# 03_ADV7511_HDMI_OUT.net
KiCad netlist of a schematic drawn in Altium Designer
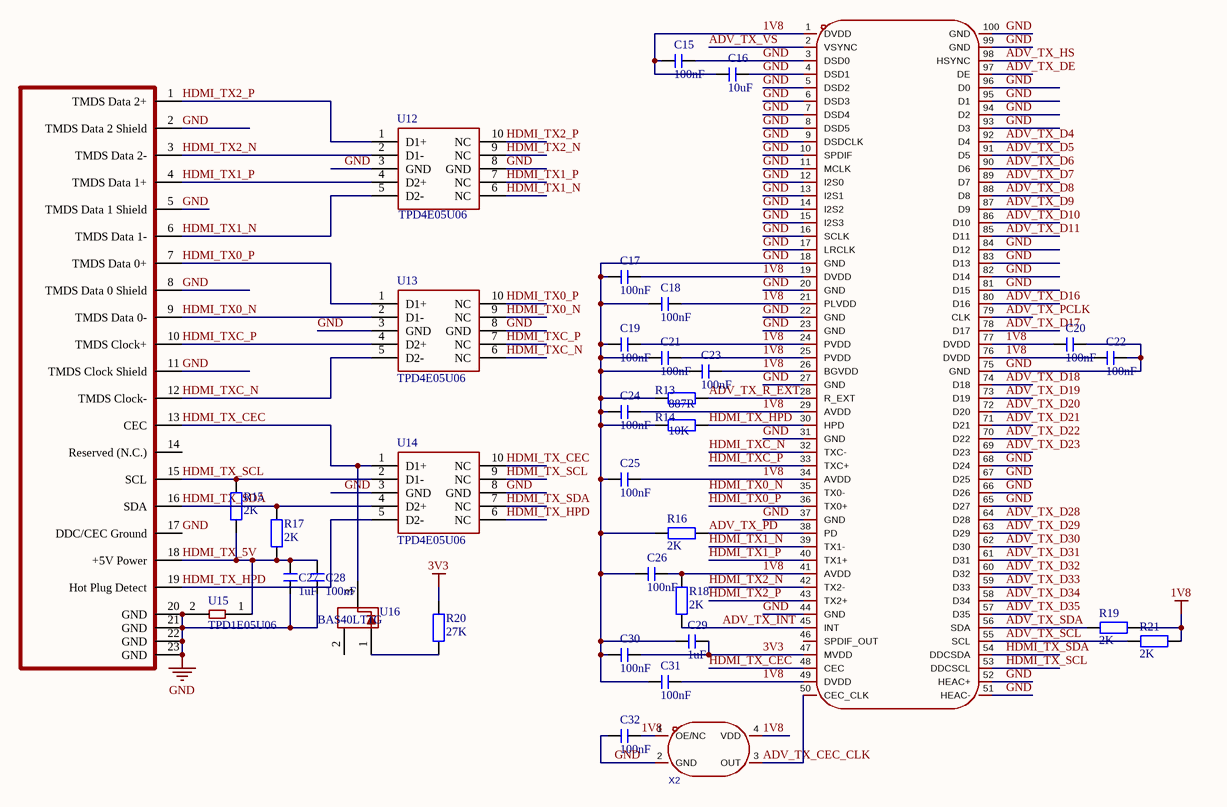
[diagram p0: 03_ADV7511_HDMI_OUT.SchDoc]

(export (version "E")
  (design (tool "Eeschema 10.0.6"))
  (components
    (comp (ref "C15")
      (value "100nF")
      (footprint "C 0603_L")
      (description "贴片电容")
      (libsource (lib "Xilinx_XCKU040_Ext_Board") (part "C"))
    )
    (comp (ref "C16")
      (value "10uF")
      (footprint "C 0603_L")
      (description "贴片电容")
      (libsource (lib "Xilinx_XCKU040_Ext_Board") (part "C"))
    )
    (comp (ref "C17")
      (value "100nF")
      (footprint "C 0603_L")
      (description "贴片电容")
      (libsource (lib "Xilinx_XCKU040_Ext_Board") (part "C"))
    )
    (comp (ref "C18")
      (value "100nF")
      (footprint "C 0603_L")
      (description "贴片电容")
      (libsource (lib "Xilinx_XCKU040_Ext_Board") (part "C"))
    )
    (comp (ref "C19")
      (value "100nF")
      (footprint "C 0603_L")
      (description "贴片电容")
      (libsource (lib "Xilinx_XCKU040_Ext_Board") (part "C"))
    )
    (comp (ref "C20")
      (value "100nF")
      (footprint "C 0603_L")
      (description "贴片电容")
      (libsource (lib "Xilinx_XCKU040_Ext_Board") (part "C"))
    )
    (comp (ref "C21")
      (value "100nF")
      (footprint "C 0603_L")
      (description "贴片电容")
      (libsource (lib "Xilinx_XCKU040_Ext_Board") (part "C"))
    )
    (comp (ref "C22")
      (value "100nF")
      (footprint "C 0603_L")
      (description "贴片电容")
      (libsource (lib "Xilinx_XCKU040_Ext_Board") (part "C"))
    )
    (comp (ref "C23")
      (value "100nF")
      (footprint "C 0603_L")
      (description "贴片电容")
      (libsource (lib "Xilinx_XCKU040_Ext_Board") (part "C"))
    )
    (comp (ref "C24")
      (value "100nF")
      (footprint "C 0603_L")
      (description "贴片电容")
      (libsource (lib "Xilinx_XCKU040_Ext_Board") (part "C"))
    )
    (comp (ref "C25")
      (value "100nF")
      (footprint "C 0603_L")
      (description "贴片电容")
      (libsource (lib "Xilinx_XCKU040_Ext_Board") (part "C"))
    )
    (comp (ref "C26")
      (value "100nF")
      (footprint "C 0603_L")
      (description "贴片电容")
      (libsource (lib "Xilinx_XCKU040_Ext_Board") (part "C"))
    )
    (comp (ref "C27")
      (value "1uF")
      (footprint "C 0603_L")
      (description "贴片电容")
      (libsource (lib "Xilinx_XCKU040_Ext_Board") (part "C"))
    )
    (comp (ref "C28")
      (value "100nF")
      (footprint "C 0603_L")
      (description "贴片电容")
      (libsource (lib "Xilinx_XCKU040_Ext_Board") (part "C"))
    )
    (comp (ref "C29")
      (value "1uF")
      (footprint "C 0603_L")
      (description "贴片电容")
      (libsource (lib "Xilinx_XCKU040_Ext_Board") (part "C"))
    )
    (comp (ref "C30")
      (value "100nF")
      (footprint "C 0603_L")
      (description "贴片电容")
      (libsource (lib "Xilinx_XCKU040_Ext_Board") (part "C"))
    )
    (comp (ref "C31")
      (value "100nF")
      (footprint "C 0603_L")
      (description "贴片电容")
      (libsource (lib "Xilinx_XCKU040_Ext_Board") (part "C"))
    )
    (comp (ref "C32")
      (value "100nF")
      (footprint "C 0603_L")
      (description "贴片电容")
      (libsource (lib "Xilinx_XCKU040_Ext_Board") (part "C"))
    )
    (comp (ref "R13")
      (value "887R")
      (footprint "R 0603_L")
      (description "贴片电阻1%")
      (fields (field (name "版权归属") "来自淘宝 ID：黄晶宝石"))
      (libsource (lib "Xilinx_XCKU040_Ext_Board") (part "R"))
    )
    (comp (ref "R14")
      (value "10K")
      (footprint "R 0603_L")
      (description "贴片电阻")
      (fields (field (name "版权归属") "来自淘宝 ID：黄晶宝石"))
      (libsource (lib "Xilinx_XCKU040_Ext_Board") (part "R"))
    )
    (comp (ref "R15")
      (value "2K")
      (footprint "R 0603_L")
      (description "贴片电阻")
      (fields (field (name "版权归属") "来自淘宝 ID：黄晶宝石"))
      (libsource (lib "Xilinx_XCKU040_Ext_Board") (part "R"))
    )
    (comp (ref "R16")
      (value "2K")
      (footprint "R 0603_L")
      (description "贴片电阻")
      (fields (field (name "版权归属") "来自淘宝 ID：黄晶宝石"))
      (libsource (lib "Xilinx_XCKU040_Ext_Board") (part "R"))
    )
    (comp (ref "R17")
      (value "2K")
      (footprint "R 0603_L")
      (description "贴片电阻")
      (fields (field (name "版权归属") "来自淘宝 ID：黄晶宝石"))
      (libsource (lib "Xilinx_XCKU040_Ext_Board") (part "R"))
    )
    (comp (ref "R18")
      (value "2K")
      (footprint "R 0603_L")
      (description "贴片电阻")
      (fields (field (name "版权归属") "来自淘宝 ID：黄晶宝石"))
      (libsource (lib "Xilinx_XCKU040_Ext_Board") (part "R"))
    )
    (comp (ref "R19")
      (value "2K")
      (footprint "R 0603_L")
      (description "贴片电阻")
      (fields (field (name "版权归属") "来自淘宝 ID：黄晶宝石"))
      (libsource (lib "Xilinx_XCKU040_Ext_Board") (part "R"))
    )
    (comp (ref "R20")
      (value "27K")
      (footprint "R 0603_L")
      (description "贴片电阻")
      (fields (field (name "版权归属") "来自淘宝 ID：黄晶宝石"))
      (libsource (lib "Xilinx_XCKU040_Ext_Board") (part "R"))
    )
    (comp (ref "R21")
      (value "2K")
      (footprint "R 0603_L")
      (description "贴片电阻")
      (fields (field (name "版权归属") "来自淘宝 ID：黄晶宝石"))
      (libsource (lib "Xilinx_XCKU040_Ext_Board") (part "R"))
    )
    (comp (ref "U5")
      (value "adv7511kstz")
      (footprint "LQFP-100_L14.0-W14.0-P0.50-LS16.0-BL")
      (description "接口类型:I2S；I2C;数据速率:-;")
      (fields (field (name "MANUFACTURER") "ADI(亚德诺)") (field (name "MANUFACTURERPART") "ADV7511KSTZ"))
      (libsource (lib "0.0self_build") (part "adv7511kstz"))
    )
    (comp (ref "U12")
      (value "TPD4E05U06")
      (footprint "TPD4E05U06DQAR")
      (description "TVS 5V ESD")
      (libsource (lib "Xilinx_XCKU040_Ext_Board") (part "TPD4E05U06"))
    )
    (comp (ref "U13")
      (value "TPD4E05U06")
      (footprint "TPD4E05U06DQAR")
      (description "TVS 5V ESD")
      (libsource (lib "Xilinx_XCKU040_Ext_Board") (part "TPD4E05U06"))
    )
    (comp (ref "U14")
      (value "TPD4E05U06")
      (footprint "TPD4E05U06DQAR")
      (description "TVS 5V ESD")
      (libsource (lib "Xilinx_XCKU040_Ext_Board") (part "TPD4E05U06"))
    )
    (comp (ref "U15")
      (value "TPD1E05U06")
      (footprint "TPD1E05U06")
      (description "单通道ESD")
      (libsource (lib "Xilinx_XCKU040_Ext_Board") (part "TPD1E05U06"))
    )
    (comp (ref "U16")
      (value "BAS40LT1G")
      (footprint "BAS40LT1G")
      (description "肖特基二极管")
      (libsource (lib "Xilinx_XCKU040_Ext_Board") (part "BAS40LT1G"))
    )
    (comp (ref "USB3")
      (value "hdmi-001s")
      (footprint "HDMI-SMD_HDMI-001S")
      (description "19PIN A型前插后贴HDMI插座 铜壳")
      (fields (field (name "MANUFACTURER") "XUNPU(讯普)") (field (name "MANUFACTURERPART") "HDMI-001S"))
      (libsource (lib "Xilinx_XCKU040_Ext_Board") (part "hdmi-001s"))
    )
    (comp (ref "X2")
      (value "ot322512mjba4sl")
      (footprint "OSC-SMD_4P-L3.2-W2.5-BL")
      (description "频率:12MHz;常温频差:±10ppm;输出模式:CMOS;工作电压:1.8V~3.3V;频率稳定度:±20ppm;")
      (fields (field (name "MANUFACTURER") "YXC(扬兴晶振)") (field (name "MANUFACTURERPART") "OT322512MJBA4SL"))
      (libsource (lib "Xilinx_XCKU040_Ext_Board") (part "ot322512mjba4sl"))
    )
  )
  (nets
    (net (code "1") (name "/ADV_TX_CEC_CLK") (class "Default")
      (node (ref "U5") (pin "50") (pinfunction "CEC_CLK_50") (pintype "passive"))
      (node (ref "X2") (pin "3") (pinfunction "OUT_3") (pintype "passive"))
    )
    (net (code "2") (name "/ADV_TX_D4") (class "Default")
      (node (ref "U5") (pin "92") (pinfunction "D4_92") (pintype "passive"))
    )
    (net (code "3") (name "/ADV_TX_D5") (class "Default")
      (node (ref "U5") (pin "91") (pinfunction "D5_91") (pintype "passive"))
    )
    (net (code "4") (name "/ADV_TX_D6") (class "Default")
      (node (ref "U5") (pin "90") (pinfunction "D6_90") (pintype "passive"))
    )
    (net (code "5") (name "/ADV_TX_D7") (class "Default")
      (node (ref "U5") (pin "89") (pinfunction "D7_89") (pintype "passive"))
    )
    (net (code "6") (name "/ADV_TX_D8") (class "Default")
      (node (ref "U5") (pin "88") (pinfunction "D8_88") (pintype "passive"))
    )
    (net (code "7") (name "/ADV_TX_D9") (class "Default")
      (node (ref "U5") (pin "87") (pinfunction "D9_87") (pintype "passive"))
    )
    (net (code "8") (name "/ADV_TX_D10") (class "Default")
      (node (ref "U5") (pin "86") (pinfunction "D10_86") (pintype "passive"))
    )
    (net (code "9") (name "/ADV_TX_D11") (class "Default")
      (node (ref "U5") (pin "85") (pinfunction "D11_85") (pintype "passive"))
    )
    (net (code "10") (name "/ADV_TX_D16") (class "Default")
      (node (ref "U5") (pin "80") (pinfunction "D16_80") (pintype "passive"))
    )
    (net (code "11") (name "/ADV_TX_D17") (class "Default")
      (node (ref "U5") (pin "78") (pinfunction "D17_78") (pintype "passive"))
    )
    (net (code "12") (name "/ADV_TX_D18") (class "Default")
      (node (ref "U5") (pin "74") (pinfunction "D18_74") (pintype "passive"))
    )
    (net (code "13") (name "/ADV_TX_D19") (class "Default")
      (node (ref "U5") (pin "73") (pinfunction "D19_73") (pintype "passive"))
    )
    (net (code "14") (name "/ADV_TX_D20") (class "Default")
      (node (ref "U5") (pin "72") (pinfunction "D20_72") (pintype "passive"))
    )
    (net (code "15") (name "/ADV_TX_D21") (class "Default")
      (node (ref "U5") (pin "71") (pinfunction "D21_71") (pintype "passive"))
    )
    (net (code "16") (name "/ADV_TX_D22") (class "Default")
      (node (ref "U5") (pin "70") (pinfunction "D22_70") (pintype "passive"))
    )
    (net (code "17") (name "/ADV_TX_D23") (class "Default")
      (node (ref "U5") (pin "69") (pinfunction "D23_69") (pintype "passive"))
    )
    (net (code "18") (name "/ADV_TX_D28") (class "Default")
      (node (ref "U5") (pin "64") (pinfunction "D28_64") (pintype "passive"))
    )
    (net (code "19") (name "/ADV_TX_D29") (class "Default")
      (node (ref "U5") (pin "63") (pinfunction "D29_63") (pintype "passive"))
    )
    (net (code "20") (name "/ADV_TX_D30") (class "Default")
      (node (ref "U5") (pin "62") (pinfunction "D30_62") (pintype "passive"))
    )
    (net (code "21") (name "/ADV_TX_D31") (class "Default")
      (node (ref "U5") (pin "61") (pinfunction "D31_61") (pintype "passive"))
    )
    (net (code "22") (name "/ADV_TX_D32") (class "Default")
      (node (ref "U5") (pin "60") (pinfunction "D32_60") (pintype "passive"))
    )
    (net (code "23") (name "/ADV_TX_D33") (class "Default")
      (node (ref "U5") (pin "59") (pinfunction "D33_59") (pintype "passive"))
    )
    (net (code "24") (name "/ADV_TX_D34") (class "Default")
      (node (ref "U5") (pin "58") (pinfunction "D34_58") (pintype "passive"))
    )
    (net (code "25") (name "/ADV_TX_D35") (class "Default")
      (node (ref "U5") (pin "57") (pinfunction "D35_57") (pintype "passive"))
    )
    (net (code "26") (name "/ADV_TX_DE") (class "Default")
      (node (ref "U5") (pin "97") (pinfunction "DE_97") (pintype "passive"))
    )
    (net (code "27") (name "/ADV_TX_HS") (class "Default")
      (node (ref "U5") (pin "98") (pinfunction "HSYNC_98") (pintype "passive"))
    )
    (net (code "28") (name "/ADV_TX_INT") (class "Default")
      (node (ref "R18") (pin "2") (pinfunction "2_2") (pintype "passive"))
      (node (ref "U5") (pin "45") (pinfunction "INT_45") (pintype "passive"))
    )
    (net (code "29") (name "/ADV_TX_PCLK") (class "Default")
      (node (ref "U5") (pin "79") (pinfunction "CLK_79") (pintype "passive"))
    )
    (net (code "30") (name "/ADV_TX_PD") (class "Default")
      (node (ref "R16") (pin "2") (pinfunction "2_2") (pintype "passive"))
      (node (ref "U5") (pin "38") (pinfunction "PD_38") (pintype "passive"))
    )
    (net (code "31") (name "/ADV_TX_R_EXT") (class "Default")
      (node (ref "R13") (pin "2") (pinfunction "2_2") (pintype "passive"))
      (node (ref "U5") (pin "28") (pinfunction "R_EXT_28") (pintype "passive"))
    )
    (net (code "32") (name "/ADV_TX_SCL") (class "Default")
      (node (ref "R21") (pin "1") (pinfunction "1_1") (pintype "passive"))
      (node (ref "U5") (pin "55") (pinfunction "SCL_55") (pintype "passive"))
    )
    (net (code "33") (name "/ADV_TX_SDA") (class "Default")
      (node (ref "R19") (pin "1") (pinfunction "1_1") (pintype "passive"))
      (node (ref "U5") (pin "56") (pinfunction "SDA_56") (pintype "passive"))
    )
    (net (code "34") (name "/ADV_TX_VS") (class "Default")
      (node (ref "U5") (pin "2") (pinfunction "VSYNC_2") (pintype "passive"))
    )
    (net (code "35") (name "/HDMI_TX0_N") (class "Default")
      (node (ref "U13") (pin "2") (pinfunction "D1-_2") (pintype "passive"))
      (node (ref "U13") (pin "9") (pinfunction "NC_9") (pintype "passive"))
      (node (ref "U5") (pin "35") (pinfunction "TX0-_35") (pintype "passive"))
      (node (ref "USB3") (pin "9") (pinfunction "TMDS_Data_0-_9") (pintype "passive"))
    )
    (net (code "36") (name "/HDMI_TX0_P") (class "Default")
      (node (ref "U13") (pin "1") (pinfunction "D1+_1") (pintype "passive"))
      (node (ref "U13") (pin "10") (pinfunction "NC_10") (pintype "passive"))
      (node (ref "U5") (pin "36") (pinfunction "TX0+_36") (pintype "passive"))
      (node (ref "USB3") (pin "7") (pinfunction "TMDS_Data_0+_7") (pintype "passive"))
    )
    (net (code "37") (name "/HDMI_TX1_N") (class "Default")
      (node (ref "U12") (pin "5") (pinfunction "D2-_5") (pintype "passive"))
      (node (ref "U12") (pin "6") (pinfunction "NC_6") (pintype "passive"))
      (node (ref "U5") (pin "39") (pinfunction "TX1-_39") (pintype "passive"))
      (node (ref "USB3") (pin "6") (pinfunction "TMDS_Data_1-_6") (pintype "passive"))
    )
    (net (code "38") (name "/HDMI_TX1_P") (class "Default")
      (node (ref "U12") (pin "4") (pinfunction "D2+_4") (pintype "passive"))
      (node (ref "U12") (pin "7") (pinfunction "NC_7") (pintype "passive"))
      (node (ref "U5") (pin "40") (pinfunction "TX1+_40") (pintype "passive"))
      (node (ref "USB3") (pin "4") (pinfunction "TMDS_Data_1+_4") (pintype "passive"))
    )
    (net (code "39") (name "/HDMI_TX2_N") (class "Default")
      (node (ref "U12") (pin "2") (pinfunction "D1-_2") (pintype "passive"))
      (node (ref "U12") (pin "9") (pinfunction "NC_9") (pintype "passive"))
      (node (ref "U5") (pin "42") (pinfunction "TX2-_42") (pintype "passive"))
      (node (ref "USB3") (pin "3") (pinfunction "TMDS_Data_2-_3") (pintype "passive"))
    )
    (net (code "40") (name "/HDMI_TX2_P") (class "Default")
      (node (ref "U12") (pin "1") (pinfunction "D1+_1") (pintype "passive"))
      (node (ref "U12") (pin "10") (pinfunction "NC_10") (pintype "passive"))
      (node (ref "U5") (pin "43") (pinfunction "TX2+_43") (pintype "passive"))
      (node (ref "USB3") (pin "1") (pinfunction "TMDS_Data_2+_1") (pintype "passive"))
    )
    (net (code "41") (name "/HDMI_TXC_N") (class "Default")
      (node (ref "U13") (pin "5") (pinfunction "D2-_5") (pintype "passive"))
      (node (ref "U13") (pin "6") (pinfunction "NC_6") (pintype "passive"))
      (node (ref "U5") (pin "32") (pinfunction "TXC-_32") (pintype "passive"))
      (node (ref "USB3") (pin "12") (pinfunction "TMDS_Clock-_12") (pintype "passive"))
    )
    (net (code "42") (name "/HDMI_TXC_P") (class "Default")
      (node (ref "U13") (pin "4") (pinfunction "D2+_4") (pintype "passive"))
      (node (ref "U13") (pin "7") (pinfunction "NC_7") (pintype "passive"))
      (node (ref "U5") (pin "33") (pinfunction "TXC+_33") (pintype "passive"))
      (node (ref "USB3") (pin "10") (pinfunction "TMDS_Clock+_10") (pintype "passive"))
    )
    (net (code "43") (name "/HDMI_TX_5V") (class "Default")
      (node (ref "C27") (pin "1") (pinfunction "1_1") (pintype "passive"))
      (node (ref "C28") (pin "1") (pinfunction "1_1") (pintype "passive"))
      (node (ref "R15") (pin "1") (pinfunction "1_1") (pintype "passive"))
      (node (ref "R17") (pin "1") (pinfunction "1_1") (pintype "passive"))
      (node (ref "U15") (pin "1") (pinfunction "IO_1") (pintype "passive"))
      (node (ref "USB3") (pin "18") (pinfunction "+5V_Power_18") (pintype "passive"))
    )
    (net (code "44") (name "/HDMI_TX_CEC") (class "Default")
      (node (ref "U14") (pin "1") (pinfunction "D1+_1") (pintype "passive"))
      (node (ref "U14") (pin "10") (pinfunction "NC_10") (pintype "passive"))
      (node (ref "U16") (pin "3") (pinfunction "3_3") (pintype "passive"))
      (node (ref "U5") (pin "48") (pinfunction "CEC_48") (pintype "passive"))
      (node (ref "USB3") (pin "13") (pinfunction "CEC_13") (pintype "passive"))
    )
    (net (code "45") (name "/HDMI_TX_HPD") (class "Default")
      (node (ref "R14") (pin "2") (pinfunction "2_2") (pintype "passive"))
      (node (ref "U14") (pin "5") (pinfunction "D2-_5") (pintype "passive"))
      (node (ref "U14") (pin "6") (pinfunction "NC_6") (pintype "passive"))
      (node (ref "U5") (pin "30") (pinfunction "HPD_30") (pintype "passive"))
      (node (ref "USB3") (pin "19") (pinfunction "Hot_Plug_Detect_19") (pintype "passive"))
    )
    (net (code "46") (name "/HDMI_TX_SCL") (class "Default")
      (node (ref "R15") (pin "2") (pinfunction "2_2") (pintype "passive"))
      (node (ref "U14") (pin "2") (pinfunction "D1-_2") (pintype "passive"))
      (node (ref "U14") (pin "9") (pinfunction "NC_9") (pintype "passive"))
      (node (ref "U5") (pin "53") (pinfunction "DDCSCL_53") (pintype "passive"))
      (node (ref "USB3") (pin "15") (pinfunction "SCL_15") (pintype "passive"))
    )
    (net (code "47") (name "/HDMI_TX_SDA") (class "Default")
      (node (ref "R17") (pin "2") (pinfunction "2_2") (pintype "passive"))
      (node (ref "U14") (pin "4") (pinfunction "D2+_4") (pintype "passive"))
      (node (ref "U14") (pin "7") (pinfunction "NC_7") (pintype "passive"))
      (node (ref "U5") (pin "54") (pinfunction "DDCSDA_54") (pintype "passive"))
      (node (ref "USB3") (pin "16") (pinfunction "SDA_16") (pintype "passive"))
    )
    (net (code "48") (name "1V8") (class "Default")
      (node (ref "C15") (pin "2") (pinfunction "2_2") (pintype "passive"))
      (node (ref "C16") (pin "2") (pinfunction "2_2") (pintype "passive"))
      (node (ref "C17") (pin "1") (pinfunction "1_1") (pintype "passive"))
      (node (ref "C18") (pin "1") (pinfunction "1_1") (pintype "passive"))
      (node (ref "C19") (pin "1") (pinfunction "1_1") (pintype "passive"))
      (node (ref "C20") (pin "2") (pinfunction "2_2") (pintype "passive"))
      (node (ref "C21") (pin "1") (pinfunction "1_1") (pintype "passive"))
      (node (ref "C22") (pin "2") (pinfunction "2_2") (pintype "passive"))
      (node (ref "C23") (pin "1") (pinfunction "1_1") (pintype "passive"))
      (node (ref "C24") (pin "1") (pinfunction "1_1") (pintype "passive"))
      (node (ref "C25") (pin "1") (pinfunction "1_1") (pintype "passive"))
      (node (ref "C26") (pin "1") (pinfunction "1_1") (pintype "passive"))
      (node (ref "C31") (pin "1") (pinfunction "1_1") (pintype "passive"))
      (node (ref "C32") (pin "1") (pinfunction "1_1") (pintype "passive"))
      (node (ref "R18") (pin "1") (pinfunction "1_1") (pintype "passive"))
      (node (ref "R19") (pin "2") (pinfunction "2_2") (pintype "passive"))
      (node (ref "R21") (pin "2") (pinfunction "2_2") (pintype "passive"))
      (node (ref "U5") (pin "1") (pinfunction "DVDD_1") (pintype "passive"))
      (node (ref "U5") (pin "19") (pinfunction "DVDD_19") (pintype "passive"))
      (node (ref "U5") (pin "21") (pinfunction "PLVDD_21") (pintype "passive"))
      (node (ref "U5") (pin "24") (pinfunction "PVDD_24") (pintype "passive"))
      (node (ref "U5") (pin "25") (pinfunction "PVDD_25") (pintype "passive"))
      (node (ref "U5") (pin "26") (pinfunction "BGVDD_26") (pintype "passive"))
      (node (ref "U5") (pin "29") (pinfunction "AVDD_29") (pintype "passive"))
      (node (ref "U5") (pin "34") (pinfunction "AVDD_34") (pintype "passive"))
      (node (ref "U5") (pin "41") (pinfunction "AVDD_41") (pintype "passive"))
      (node (ref "U5") (pin "49") (pinfunction "DVDD_49") (pintype "passive"))
      (node (ref "U5") (pin "76") (pinfunction "DVDD_76") (pintype "passive"))
      (node (ref "U5") (pin "77") (pinfunction "DVDD_77") (pintype "passive"))
      (node (ref "X2") (pin "1") (pinfunction "OE/NC_1") (pintype "passive"))
      (node (ref "X2") (pin "4") (pinfunction "VDD_4") (pintype "passive"))
    )
    (net (code "49") (name "3V3") (class "Default")
      (node (ref "C29") (pin "1") (pinfunction "1_1") (pintype "passive"))
      (node (ref "C30") (pin "1") (pinfunction "1_1") (pintype "passive"))
      (node (ref "R20") (pin "2") (pinfunction "2_2") (pintype "passive"))
      (node (ref "U5") (pin "47") (pinfunction "MVDD_47") (pintype "passive"))
    )
    (net (code "50") (name "GND") (class "Default")
      (node (ref "C15") (pin "1") (pinfunction "1_1") (pintype "passive"))
      (node (ref "C16") (pin "1") (pinfunction "1_1") (pintype "passive"))
      (node (ref "C17") (pin "2") (pinfunction "2_2") (pintype "passive"))
      (node (ref "C18") (pin "2") (pinfunction "2_2") (pintype "passive"))
      (node (ref "C19") (pin "2") (pinfunction "2_2") (pintype "passive"))
      (node (ref "C20") (pin "1") (pinfunction "1_1") (pintype "passive"))
      (node (ref "C21") (pin "2") (pinfunction "2_2") (pintype "passive"))
      (node (ref "C22") (pin "1") (pinfunction "1_1") (pintype "passive"))
      (node (ref "C23") (pin "2") (pinfunction "2_2") (pintype "passive"))
      (node (ref "C24") (pin "2") (pinfunction "2_2") (pintype "passive"))
      (node (ref "C25") (pin "2") (pinfunction "2_2") (pintype "passive"))
      (node (ref "C26") (pin "2") (pinfunction "2_2") (pintype "passive"))
      (node (ref "C27") (pin "2") (pinfunction "2_2") (pintype "passive"))
      (node (ref "C28") (pin "2") (pinfunction "2_2") (pintype "passive"))
      (node (ref "C29") (pin "2") (pinfunction "2_2") (pintype "passive"))
      (node (ref "C30") (pin "2") (pinfunction "2_2") (pintype "passive"))
      (node (ref "C31") (pin "2") (pinfunction "2_2") (pintype "passive"))
      (node (ref "C32") (pin "2") (pinfunction "2_2") (pintype "passive"))
      (node (ref "R13") (pin "1") (pinfunction "1_1") (pintype "passive"))
      (node (ref "R14") (pin "1") (pinfunction "1_1") (pintype "passive"))
      (node (ref "R16") (pin "1") (pinfunction "1_1") (pintype "passive"))
      (node (ref "U12") (pin "3") (pinfunction "GND_3") (pintype "passive"))
      (node (ref "U12") (pin "8") (pinfunction "GND_8") (pintype "passive"))
      (node (ref "U13") (pin "3") (pinfunction "GND_3") (pintype "passive"))
      (node (ref "U13") (pin "8") (pinfunction "GND_8") (pintype "passive"))
      (node (ref "U14") (pin "3") (pinfunction "GND_3") (pintype "passive"))
      (node (ref "U14") (pin "8") (pinfunction "GND_8") (pintype "passive"))
      (node (ref "U15") (pin "2") (pinfunction "GND_2") (pintype "passive"))
      (node (ref "U5") (pin "10") (pinfunction "SPDIF_10") (pintype "passive"))
      (node (ref "U5") (pin "100") (pinfunction "GND_100") (pintype "passive"))
      (node (ref "U5") (pin "11") (pinfunction "MCLK_11") (pintype "passive"))
      (node (ref "U5") (pin "12") (pinfunction "I2S0_12") (pintype "passive"))
      (node (ref "U5") (pin "13") (pinfunction "I2S1_13") (pintype "passive"))
      (node (ref "U5") (pin "14") (pinfunction "I2S2_14") (pintype "passive"))
      (node (ref "U5") (pin "15") (pinfunction "I2S3_15") (pintype "passive"))
      (node (ref "U5") (pin "16") (pinfunction "SCLK_16") (pintype "passive"))
      (node (ref "U5") (pin "17") (pinfunction "LRCLK_17") (pintype "passive"))
      (node (ref "U5") (pin "18") (pinfunction "GND_18") (pintype "passive"))
      (node (ref "U5") (pin "20") (pinfunction "GND_20") (pintype "passive"))
      (node (ref "U5") (pin "22") (pinfunction "GND_22") (pintype "passive"))
      (node (ref "U5") (pin "23") (pinfunction "GND_23") (pintype "passive"))
      (node (ref "U5") (pin "27") (pinfunction "GND_27") (pintype "passive"))
      (node (ref "U5") (pin "3") (pinfunction "DSD0_3") (pintype "passive"))
      (node (ref "U5") (pin "31") (pinfunction "GND_31") (pintype "passive"))
      (node (ref "U5") (pin "37") (pinfunction "GND_37") (pintype "passive"))
      (node (ref "U5") (pin "4") (pinfunction "DSD1_4") (pintype "passive"))
      (node (ref "U5") (pin "44") (pinfunction "GND_44") (pintype "passive"))
      (node (ref "U5") (pin "5") (pinfunction "DSD2_5") (pintype "passive"))
      (node (ref "U5") (pin "51") (pinfunction "HEAC-_51") (pintype "passive"))
      (node (ref "U5") (pin "52") (pinfunction "HEAC+_52") (pintype "passive"))
      (node (ref "U5") (pin "6") (pinfunction "DSD3_6") (pintype "passive"))
      (node (ref "U5") (pin "65") (pinfunction "D27_65") (pintype "passive"))
      (node (ref "U5") (pin "66") (pinfunction "D26_66") (pintype "passive"))
      (node (ref "U5") (pin "67") (pinfunction "D25_67") (pintype "passive"))
      (node (ref "U5") (pin "68") (pinfunction "D24_68") (pintype "passive"))
      (node (ref "U5") (pin "7") (pinfunction "DSD4_7") (pintype "passive"))
      (node (ref "U5") (pin "75") (pinfunction "GND_75") (pintype "passive"))
      (node (ref "U5") (pin "8") (pinfunction "DSD5_8") (pintype "passive"))
      (node (ref "U5") (pin "81") (pinfunction "D15_81") (pintype "passive"))
      (node (ref "U5") (pin "82") (pinfunction "D14_82") (pintype "passive"))
      (node (ref "U5") (pin "83") (pinfunction "D13_83") (pintype "passive"))
      (node (ref "U5") (pin "84") (pinfunction "D12_84") (pintype "passive"))
      (node (ref "U5") (pin "9") (pinfunction "DSDCLK_9") (pintype "passive"))
      (node (ref "U5") (pin "93") (pinfunction "D3_93") (pintype "passive"))
      (node (ref "U5") (pin "94") (pinfunction "D2_94") (pintype "passive"))
      (node (ref "U5") (pin "95") (pinfunction "D1_95") (pintype "passive"))
      (node (ref "U5") (pin "96") (pinfunction "D0_96") (pintype "passive"))
      (node (ref "U5") (pin "99") (pinfunction "GND_99") (pintype "passive"))
      (node (ref "USB3") (pin "11") (pinfunction "TMDS_Clock_Shield_11") (pintype "passive"))
      (node (ref "USB3") (pin "17") (pinfunction "DDC/CEC_Ground_17") (pintype "passive"))
      (node (ref "USB3") (pin "2") (pinfunction "TMDS_Data_2_Shield_2") (pintype "passive"))
      (node (ref "USB3") (pin "20") (pinfunction "GND_20") (pintype "passive"))
      (node (ref "USB3") (pin "21") (pinfunction "GND_21") (pintype "passive"))
      (node (ref "USB3") (pin "22") (pinfunction "GND_22") (pintype "passive"))
      (node (ref "USB3") (pin "23") (pinfunction "GND_23") (pintype "passive"))
      (node (ref "USB3") (pin "5") (pinfunction "TMDS_Data_1_Shield_5") (pintype "passive"))
      (node (ref "USB3") (pin "8") (pinfunction "TMDS_Data_0_Shield_8") (pintype "passive"))
      (node (ref "X2") (pin "2") (pinfunction "GND_2") (pintype "passive"))
    )
    (net (code "51") (name "Net-(R20-Pad1)") (class "Default")
      (node (ref "R20") (pin "1") (pinfunction "1_1") (pintype "passive"))
      (node (ref "U16") (pin "1") (pinfunction "1_1") (pintype "passive"))
    )
    (net (code "52") (name "unconnected-(U5-SPDIF_OUT-Pad46)") (class "Default")
      (node (ref "U5") (pin "46") (pinfunction "SPDIF_OUT_46") (pintype "passive"))
    )
    (net (code "53") (name "unconnected-(U16-Pad2)") (class "Default")
      (node (ref "U16") (pin "2") (pinfunction "2_2") (pintype "passive"))
    )
    (net (code "54") (name "unconnected-(USB3-Reserved_(N.C.)-Pad14)") (class "Default")
      (node (ref "USB3") (pin "14") (pinfunction "Reserved_(N.C.)_14") (pintype "passive"))
    )
  )
)
